# io_TS.net
KiCad netlist of a schematic drawn in Altium Designer
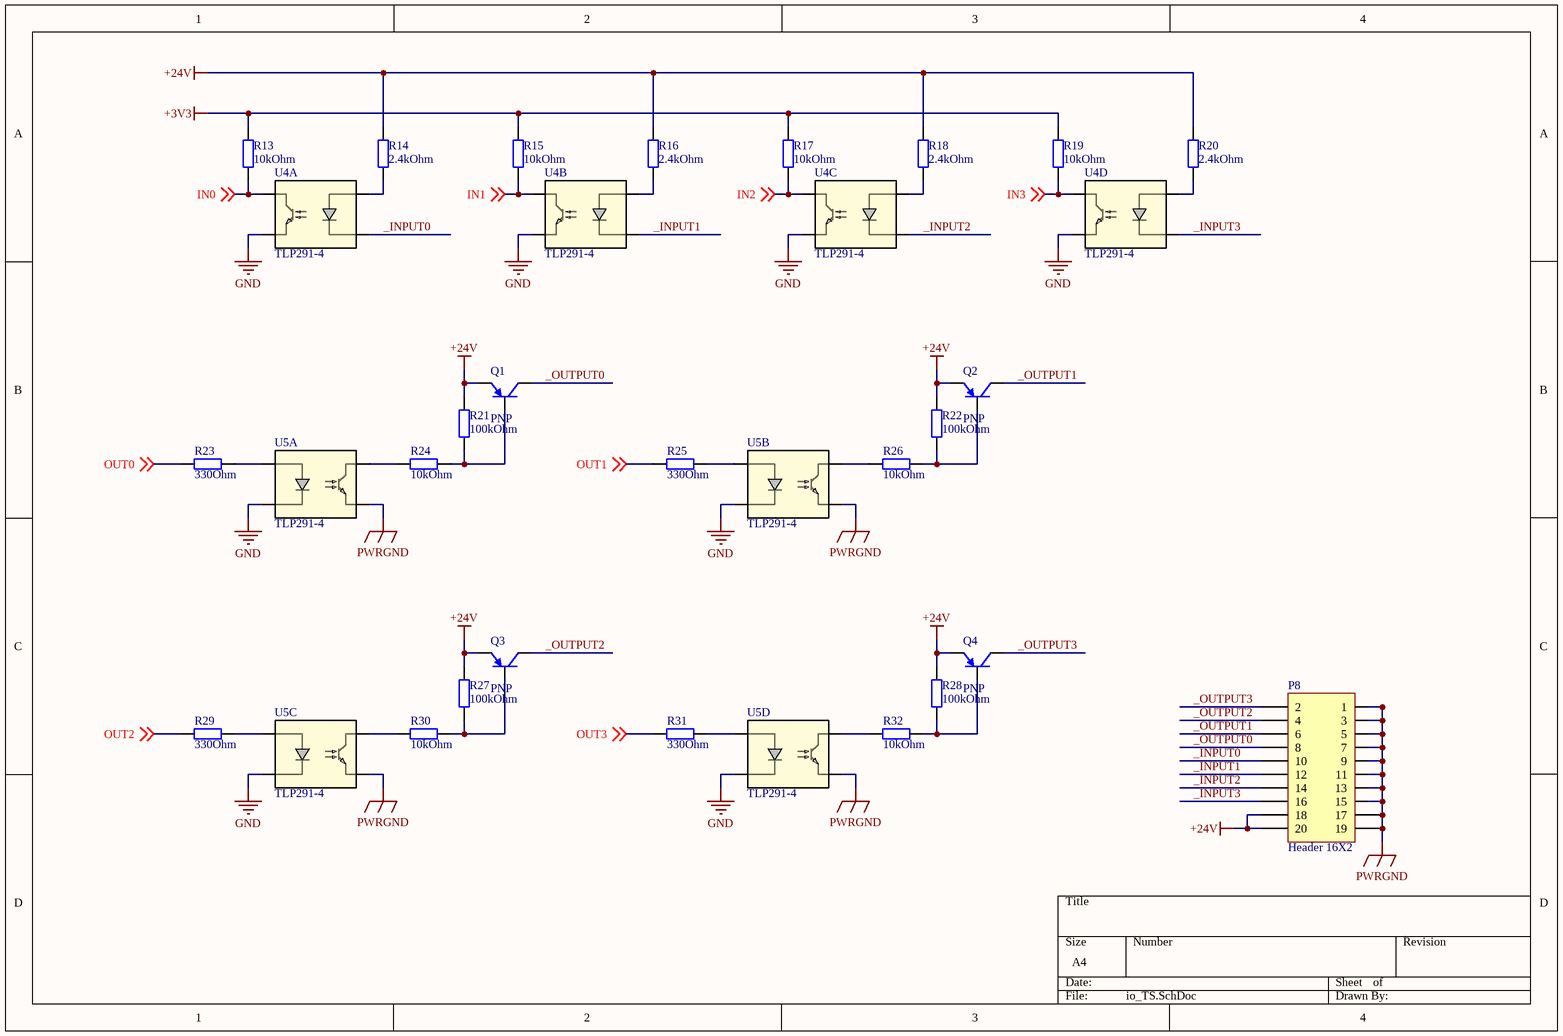
[diagram p0: io_TS.SchDoc]

(export (version "E")
  (design (tool "Eeschema 10.0.6"))
  (components
    (comp (ref "P8")
      (value "Header 16X2")
      (footprint "MOLEX 505448-2071")
      (description "Header, 32-Pin")
      (fields (field (name "PUBLISHER") "Altium Limited"))
      (libsource (lib "MiLib") (part "Header 10X2"))
    )
    (comp (ref "Q1")
      (value "PNP")
      (footprint "SOT-89")
      (description "PNP Bipolar Transistor (for SOT23-3 only).")
      (fields (field (name "PUBLISHER") "Altium Limited"))
      (libsource (lib "MiLib") (part "PNP"))
    )
    (comp (ref "Q2")
      (value "PNP")
      (footprint "SOT-89")
      (description "PNP Bipolar Transistor (for SOT23-3 only).")
      (fields (field (name "PUBLISHER") "Altium Limited"))
      (libsource (lib "MiLib") (part "PNP"))
    )
    (comp (ref "Q3")
      (value "PNP")
      (footprint "SOT-89")
      (description "PNP Bipolar Transistor (for SOT23-3 only).")
      (fields (field (name "PUBLISHER") "Altium Limited"))
      (libsource (lib "MiLib") (part "PNP"))
    )
    (comp (ref "Q4")
      (value "PNP")
      (footprint "SOT-89")
      (description "PNP Bipolar Transistor (for SOT23-3 only).")
      (fields (field (name "PUBLISHER") "Altium Limited"))
      (libsource (lib "MiLib") (part "PNP"))
    )
    (comp (ref "R13")
      (value "10kOhm")
      (footprint "RES 0805")
      (description "Resistor")
      (fields (field (name "PUBLISHER") "Altium Limited"))
      (libsource (lib "") (part "Res_1"))
    )
    (comp (ref "R14")
      (value "2.4kOhm")
      (footprint "RES 0805")
      (description "Resistor")
      (fields (field (name "PUBLISHER") "Altium Limited"))
      (libsource (lib "") (part "Res_1"))
    )
    (comp (ref "R15")
      (value "10kOhm")
      (footprint "RES 0805")
      (description "Resistor")
      (fields (field (name "PUBLISHER") "Altium Limited"))
      (libsource (lib "") (part "Res_1"))
    )
    (comp (ref "R16")
      (value "2.4kOhm")
      (footprint "RES 0805")
      (description "Resistor")
      (fields (field (name "PUBLISHER") "Altium Limited"))
      (libsource (lib "") (part "Res_1"))
    )
    (comp (ref "R17")
      (value "10kOhm")
      (footprint "RES 0805")
      (description "Resistor")
      (fields (field (name "PUBLISHER") "Altium Limited"))
      (libsource (lib "") (part "Res_1"))
    )
    (comp (ref "R18")
      (value "2.4kOhm")
      (footprint "RES 0805")
      (description "Resistor")
      (fields (field (name "PUBLISHER") "Altium Limited"))
      (libsource (lib "") (part "Res_1"))
    )
    (comp (ref "R19")
      (value "10kOhm")
      (footprint "RES 0805")
      (description "Resistor")
      (fields (field (name "PUBLISHER") "Altium Limited"))
      (libsource (lib "") (part "Res_1"))
    )
    (comp (ref "R20")
      (value "2.4kOhm")
      (footprint "RES 0805")
      (description "Resistor")
      (fields (field (name "PUBLISHER") "Altium Limited"))
      (libsource (lib "") (part "Res_1"))
    )
    (comp (ref "R21")
      (value "100kOhm")
      (footprint "RES 0805")
      (description "Resistor")
      (fields (field (name "PUBLISHER") "Altium Limited"))
      (libsource (lib "") (part "Res_1"))
    )
    (comp (ref "R22")
      (value "100kOhm")
      (footprint "RES 0805")
      (description "Resistor")
      (fields (field (name "PUBLISHER") "Altium Limited"))
      (libsource (lib "") (part "Res_1"))
    )
    (comp (ref "R23")
      (value "330Ohm")
      (footprint "RES 0805")
      (description "Resistor")
      (fields (field (name "PUBLISHER") "Altium Limited"))
      (libsource (lib "MiLib") (part "Res"))
    )
    (comp (ref "R24")
      (value "10kOhm")
      (footprint "RES 0805")
      (description "Resistor")
      (fields (field (name "PUBLISHER") "Altium Limited"))
      (libsource (lib "MiLib") (part "Res"))
    )
    (comp (ref "R25")
      (value "330Ohm")
      (footprint "RES 0805")
      (description "Resistor")
      (fields (field (name "PUBLISHER") "Altium Limited"))
      (libsource (lib "MiLib") (part "Res"))
    )
    (comp (ref "R26")
      (value "10kOhm")
      (footprint "RES 0805")
      (description "Resistor")
      (fields (field (name "PUBLISHER") "Altium Limited"))
      (libsource (lib "MiLib") (part "Res"))
    )
    (comp (ref "R27")
      (value "100kOhm")
      (footprint "RES 0805")
      (description "Resistor")
      (fields (field (name "PUBLISHER") "Altium Limited"))
      (libsource (lib "") (part "Res_1"))
    )
    (comp (ref "R28")
      (value "100kOhm")
      (footprint "RES 0805")
      (description "Resistor")
      (fields (field (name "PUBLISHER") "Altium Limited"))
      (libsource (lib "") (part "Res_1"))
    )
    (comp (ref "R29")
      (value "330Ohm")
      (footprint "RES 0805")
      (description "Resistor")
      (fields (field (name "PUBLISHER") "Altium Limited"))
      (libsource (lib "MiLib") (part "Res"))
    )
    (comp (ref "R30")
      (value "10kOhm")
      (footprint "RES 0805")
      (description "Resistor")
      (fields (field (name "PUBLISHER") "Altium Limited"))
      (libsource (lib "MiLib") (part "Res"))
    )
    (comp (ref "R31")
      (value "330Ohm")
      (footprint "RES 0805")
      (description "Resistor")
      (fields (field (name "PUBLISHER") "Altium Limited"))
      (libsource (lib "MiLib") (part "Res"))
    )
    (comp (ref "R32")
      (value "10kOhm")
      (footprint "RES 0805")
      (description "Resistor")
      (fields (field (name "PUBLISHER") "Altium Limited"))
      (libsource (lib "MiLib") (part "Res"))
    )
    (comp (ref "U4")
      (value "TLP291-4")
      (footprint "SO-16")
      (description "No Description Available")
      (fields (field (name "COPYRIGHT") "Copyright (C) 2018 Accelerated Designs. All rights reserved"))
      (libsource (lib "misc") (part "TLP291-4"))
    )
    (comp (ref "U5")
      (value "TLP291-4")
      (footprint "SO-16")
      (description "No Description Available")
      (fields (field (name "COPYRIGHT") "Copyright (C) 2018 Accelerated Designs. All rights reserved"))
      (libsource (lib "") (part "TLP291-4_1"))
    )
  )
  (nets
    (net (code "1") (name "+3V3") (class "Default")
      (node (ref "R13") (pin "2") (pinfunction "2_2") (pintype "passive"))
      (node (ref "R15") (pin "2") (pinfunction "2_2") (pintype "passive"))
      (node (ref "R17") (pin "2") (pinfunction "2_2") (pintype "passive"))
      (node (ref "R19") (pin "2") (pinfunction "2_2") (pintype "passive"))
    )
    (net (code "2") (name "+24V") (class "Default")
      (node (ref "P8") (pin "18") (pinfunction "18_18") (pintype "passive"))
      (node (ref "P8") (pin "20") (pinfunction "20_20") (pintype "passive"))
      (node (ref "Q1") (pin "2") (pinfunction "E_2") (pintype "passive"))
      (node (ref "Q2") (pin "2") (pinfunction "E_2") (pintype "passive"))
      (node (ref "Q3") (pin "2") (pinfunction "E_2") (pintype "passive"))
      (node (ref "Q4") (pin "2") (pinfunction "E_2") (pintype "passive"))
      (node (ref "R14") (pin "2") (pinfunction "2_2") (pintype "passive"))
      (node (ref "R16") (pin "2") (pinfunction "2_2") (pintype "passive"))
      (node (ref "R18") (pin "2") (pinfunction "2_2") (pintype "passive"))
      (node (ref "R20") (pin "2") (pinfunction "2_2") (pintype "passive"))
      (node (ref "R21") (pin "2") (pinfunction "2_2") (pintype "passive"))
      (node (ref "R22") (pin "2") (pinfunction "2_2") (pintype "passive"))
      (node (ref "R27") (pin "2") (pinfunction "2_2") (pintype "passive"))
      (node (ref "R28") (pin "2") (pinfunction "2_2") (pintype "passive"))
    )
    (net (code "3") (name "/_INPUT0") (class "Default")
      (node (ref "P8") (pin "10") (pinfunction "10_10") (pintype "passive"))
      (node (ref "U4") (pin "2") (pinfunction "2_2") (pintype "passive"))
    )
    (net (code "4") (name "/_INPUT1") (class "Default")
      (node (ref "P8") (pin "12") (pinfunction "12_12") (pintype "passive"))
      (node (ref "U4") (pin "4") (pinfunction "4_4") (pintype "passive"))
    )
    (net (code "5") (name "/_INPUT2") (class "Default")
      (node (ref "P8") (pin "14") (pinfunction "14_14") (pintype "passive"))
      (node (ref "U4") (pin "6") (pinfunction "6_6") (pintype "passive"))
    )
    (net (code "6") (name "/_INPUT3") (class "Default")
      (node (ref "P8") (pin "16") (pinfunction "16_16") (pintype "passive"))
      (node (ref "U4") (pin "8") (pinfunction "8_8") (pintype "passive"))
    )
    (net (code "7") (name "/_OUTPUT0") (class "Default")
      (node (ref "P8") (pin "8") (pinfunction "8_8") (pintype "passive"))
      (node (ref "Q1") (pin "3") (pinfunction "C_3") (pintype "passive"))
    )
    (net (code "8") (name "/_OUTPUT1") (class "Default")
      (node (ref "P8") (pin "6") (pinfunction "6_6") (pintype "passive"))
      (node (ref "Q2") (pin "3") (pinfunction "C_3") (pintype "passive"))
    )
    (net (code "9") (name "/_OUTPUT2") (class "Default")
      (node (ref "P8") (pin "4") (pinfunction "4_4") (pintype "passive"))
      (node (ref "Q3") (pin "3") (pinfunction "C_3") (pintype "passive"))
    )
    (net (code "10") (name "/_OUTPUT3") (class "Default")
      (node (ref "P8") (pin "2") (pinfunction "2_2") (pintype "passive"))
      (node (ref "Q4") (pin "3") (pinfunction "C_3") (pintype "passive"))
    )
    (net (code "11") (name "GND") (class "Default")
      (node (ref "U4") (pin "11") (pinfunction "11_11") (pintype "passive"))
      (node (ref "U4") (pin "13") (pinfunction "13_13") (pintype "passive"))
      (node (ref "U4") (pin "15") (pinfunction "15_15") (pintype "passive"))
      (node (ref "U4") (pin "9") (pinfunction "9_9") (pintype "passive"))
      (node (ref "U5") (pin "2") (pinfunction "2_2") (pintype "passive"))
      (node (ref "U5") (pin "4") (pinfunction "4_4") (pintype "passive"))
      (node (ref "U5") (pin "6") (pinfunction "6_6") (pintype "passive"))
      (node (ref "U5") (pin "8") (pinfunction "8_8") (pintype "passive"))
    )
    (net (code "12") (name "IN0") (class "Default")
      (node (ref "R13") (pin "1") (pinfunction "1_1") (pintype "passive"))
      (node (ref "U4") (pin "16") (pinfunction "16_16") (pintype "passive"))
    )
    (net (code "13") (name "IN1") (class "Default")
      (node (ref "R15") (pin "1") (pinfunction "1_1") (pintype "passive"))
      (node (ref "U4") (pin "14") (pinfunction "14_14") (pintype "passive"))
    )
    (net (code "14") (name "IN2") (class "Default")
      (node (ref "R17") (pin "1") (pinfunction "1_1") (pintype "passive"))
      (node (ref "U4") (pin "12") (pinfunction "12_12") (pintype "passive"))
    )
    (net (code "15") (name "IN3") (class "Default")
      (node (ref "R19") (pin "1") (pinfunction "1_1") (pintype "passive"))
      (node (ref "U4") (pin "10") (pinfunction "10_10") (pintype "passive"))
    )
    (net (code "16") (name "Net-(Q1-B)") (class "Default")
      (node (ref "Q1") (pin "1") (pinfunction "B_1") (pintype "passive"))
      (node (ref "R21") (pin "1") (pinfunction "1_1") (pintype "passive"))
      (node (ref "R24") (pin "1") (pinfunction "1_1") (pintype "passive"))
    )
    (net (code "17") (name "Net-(Q2-B)") (class "Default")
      (node (ref "Q2") (pin "1") (pinfunction "B_1") (pintype "passive"))
      (node (ref "R22") (pin "1") (pinfunction "1_1") (pintype "passive"))
      (node (ref "R26") (pin "1") (pinfunction "1_1") (pintype "passive"))
    )
    (net (code "18") (name "Net-(Q3-B)") (class "Default")
      (node (ref "Q3") (pin "1") (pinfunction "B_1") (pintype "passive"))
      (node (ref "R27") (pin "1") (pinfunction "1_1") (pintype "passive"))
      (node (ref "R30") (pin "1") (pinfunction "1_1") (pintype "passive"))
    )
    (net (code "19") (name "Net-(Q4-B)") (class "Default")
      (node (ref "Q4") (pin "1") (pinfunction "B_1") (pintype "passive"))
      (node (ref "R28") (pin "1") (pinfunction "1_1") (pintype "passive"))
      (node (ref "R32") (pin "1") (pinfunction "1_1") (pintype "passive"))
    )
    (net (code "20") (name "Net-(R14-Pad1)") (class "Default")
      (node (ref "R14") (pin "1") (pinfunction "1_1") (pintype "passive"))
      (node (ref "U4") (pin "1") (pinfunction "1_1") (pintype "passive"))
    )
    (net (code "21") (name "Net-(R16-Pad1)") (class "Default")
      (node (ref "R16") (pin "1") (pinfunction "1_1") (pintype "passive"))
      (node (ref "U4") (pin "3") (pinfunction "3_3") (pintype "passive"))
    )
    (net (code "22") (name "Net-(R18-Pad1)") (class "Default")
      (node (ref "R18") (pin "1") (pinfunction "1_1") (pintype "passive"))
      (node (ref "U4") (pin "5") (pinfunction "5_5") (pintype "passive"))
    )
    (net (code "23") (name "Net-(R20-Pad1)") (class "Default")
      (node (ref "R20") (pin "1") (pinfunction "1_1") (pintype "passive"))
      (node (ref "U4") (pin "7") (pinfunction "7_7") (pintype "passive"))
    )
    (net (code "24") (name "Net-(R23-Pad1)") (class "Default")
      (node (ref "R23") (pin "1") (pinfunction "1_1") (pintype "passive"))
      (node (ref "U5") (pin "1") (pinfunction "1_1") (pintype "passive"))
    )
    (net (code "25") (name "Net-(R24-Pad2)") (class "Default")
      (node (ref "R24") (pin "2") (pinfunction "2_2") (pintype "passive"))
      (node (ref "U5") (pin "16") (pinfunction "16_16") (pintype "passive"))
    )
    (net (code "26") (name "Net-(R25-Pad1)") (class "Default")
      (node (ref "R25") (pin "1") (pinfunction "1_1") (pintype "passive"))
      (node (ref "U5") (pin "3") (pinfunction "3_3") (pintype "passive"))
    )
    (net (code "27") (name "Net-(R26-Pad2)") (class "Default")
      (node (ref "R26") (pin "2") (pinfunction "2_2") (pintype "passive"))
      (node (ref "U5") (pin "14") (pinfunction "14_14") (pintype "passive"))
    )
    (net (code "28") (name "Net-(R29-Pad1)") (class "Default")
      (node (ref "R29") (pin "1") (pinfunction "1_1") (pintype "passive"))
      (node (ref "U5") (pin "5") (pinfunction "5_5") (pintype "passive"))
    )
    (net (code "29") (name "Net-(R30-Pad2)") (class "Default")
      (node (ref "R30") (pin "2") (pinfunction "2_2") (pintype "passive"))
      (node (ref "U5") (pin "12") (pinfunction "12_12") (pintype "passive"))
    )
    (net (code "30") (name "Net-(R31-Pad1)") (class "Default")
      (node (ref "R31") (pin "1") (pinfunction "1_1") (pintype "passive"))
      (node (ref "U5") (pin "7") (pinfunction "7_7") (pintype "passive"))
    )
    (net (code "31") (name "Net-(R32-Pad2)") (class "Default")
      (node (ref "R32") (pin "2") (pinfunction "2_2") (pintype "passive"))
      (node (ref "U5") (pin "10") (pinfunction "10_10") (pintype "passive"))
    )
    (net (code "32") (name "OUT0") (class "Default")
      (node (ref "R23") (pin "2") (pinfunction "2_2") (pintype "passive"))
    )
    (net (code "33") (name "OUT1") (class "Default")
      (node (ref "R25") (pin "2") (pinfunction "2_2") (pintype "passive"))
    )
    (net (code "34") (name "OUT2") (class "Default")
      (node (ref "R29") (pin "2") (pinfunction "2_2") (pintype "passive"))
    )
    (net (code "35") (name "OUT3") (class "Default")
      (node (ref "R31") (pin "2") (pinfunction "2_2") (pintype "passive"))
    )
    (net (code "36") (name "PWRGND") (class "Default")
      (node (ref "P8") (pin "1") (pinfunction "1_1") (pintype "passive"))
      (node (ref "P8") (pin "11") (pinfunction "11_11") (pintype "passive"))
      (node (ref "P8") (pin "13") (pinfunction "13_13") (pintype "passive"))
      (node (ref "P8") (pin "15") (pinfunction "15_15") (pintype "passive"))
      (node (ref "P8") (pin "17") (pinfunction "17_17") (pintype "passive"))
      (node (ref "P8") (pin "19") (pinfunction "19_19") (pintype "passive"))
      (node (ref "P8") (pin "3") (pinfunction "3_3") (pintype "passive"))
      (node (ref "P8") (pin "5") (pinfunction "5_5") (pintype "passive"))
      (node (ref "P8") (pin "7") (pinfunction "7_7") (pintype "passive"))
      (node (ref "P8") (pin "9") (pinfunction "9_9") (pintype "passive"))
      (node (ref "U5") (pin "11") (pinfunction "11_11") (pintype "passive"))
      (node (ref "U5") (pin "13") (pinfunction "13_13") (pintype "passive"))
      (node (ref "U5") (pin "15") (pinfunction "15_15") (pintype "passive"))
      (node (ref "U5") (pin "9") (pinfunction "9_9") (pintype "passive"))
    )
  )
)
